# v1_5_Touch_USB.net
KiCad netlist of a schematic drawn in Altium Designer
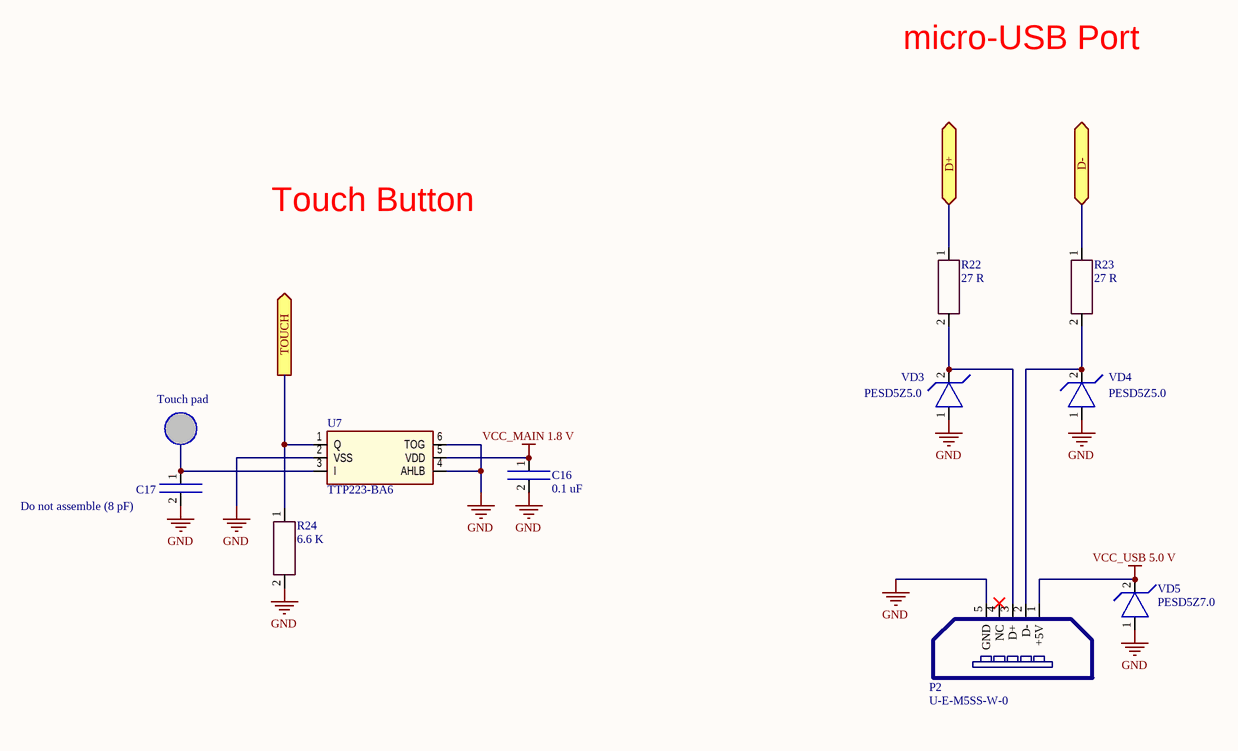
[diagram p0: v1.5 Touch & USB.SchDoc]

(export (version "E")
  (design (tool "Eeschema 10.0.6"))
  (components
    (comp (ref "C16")
      (value "0.1 uF")
      (footprint "Ungravity Library:0402")
      (libsource (lib "Ungravity Library") (part "Capasistor"))
    )
    (comp (ref "C17")
      (value "Do not assemble (8 pF)")
      (footprint "Ungravity Library:0402")
      (libsource (lib "Ungravity Library") (part "Capasistor"))
    )
    (comp (ref "P2")
      (value "U-E-M5SS-W-0")
      (footprint "Ungravity Library:U-E-M5SS-W-0")
      (libsource (lib "Ungravity Library") (part "micro-USB port"))
    )
    (comp (ref "R22")
      (value "27 R")
      (footprint "Ungravity Library:0402")
      (libsource (lib "Ungravity Library") (part "Resistor"))
    )
    (comp (ref "R23")
      (value "27 R")
      (footprint "Ungravity Library:0402")
      (libsource (lib "Ungravity Library") (part "Resistor"))
    )
    (comp (ref "R24")
      (value "6.6 K")
      (footprint "Ungravity Library:0402")
      (libsource (lib "Ungravity Library") (part "Resistor"))
    )
    (comp (ref "U7")
      (value "TTP223-BA6")
      (footprint "Ungravity Library:SOT23-6")
      (libsource (lib "Ungravity Library") (part "TTP223-BA6"))
    )
    (comp (ref "VD3")
      (value "PESD5Z5.0")
      (footprint "Ungravity Library:SOD-523")
      (libsource (lib "Ungravity Library") (part "Stabilitron"))
    )
    (comp (ref "VD4")
      (value "PESD5Z5.0")
      (footprint "Ungravity Library:SOD-523")
      (libsource (lib "Ungravity Library") (part "Stabilitron"))
    )
    (comp (ref "VD5")
      (value "PESD5Z7.0")
      (footprint "Ungravity Library:SOD-523")
      (libsource (lib "Ungravity Library") (part "Stabilitron"))
    )
  )
  (nets
    (net (code "1") (name "/D+") (class "Default")
      (node (ref "R22") (pin "1") (pinfunction "1_1") (pintype "passive"))
    )
    (net (code "2") (name "/D-") (class "Default")
      (node (ref "R23") (pin "1") (pinfunction "1_1") (pintype "passive"))
    )
    (net (code "3") (name "/TOUCH") (class "Default")
      (node (ref "R24") (pin "1") (pinfunction "1_1") (pintype "passive"))
      (node (ref "U7") (pin "1") (pinfunction "Q_1") (pintype "passive"))
    )
    (net (code "4") (name "GND") (class "Default")
      (node (ref "C16") (pin "2") (pinfunction "2_2") (pintype "passive"))
      (node (ref "C17") (pin "2") (pinfunction "2_2") (pintype "passive"))
      (node (ref "P2") (pin "5") (pinfunction "GND_5") (pintype "passive"))
      (node (ref "R24") (pin "2") (pinfunction "2_2") (pintype "passive"))
      (node (ref "U7") (pin "2") (pinfunction "VSS_2") (pintype "passive"))
      (node (ref "U7") (pin "4") (pinfunction "AHLB_4") (pintype "passive"))
      (node (ref "U7") (pin "6") (pinfunction "TOG_6") (pintype "passive"))
      (node (ref "VD3") (pin "1") (pinfunction "1_1") (pintype "passive"))
      (node (ref "VD4") (pin "1") (pinfunction "1_1") (pintype "passive"))
      (node (ref "VD5") (pin "1") (pinfunction "1_1") (pintype "passive"))
    )
    (net (code "5") (name "Net-(P2-D+)") (class "Default")
      (node (ref "P2") (pin "3") (pinfunction "D+_3") (pintype "passive"))
      (node (ref "R22") (pin "2") (pinfunction "2_2") (pintype "passive"))
      (node (ref "VD3") (pin "2") (pinfunction "2_2") (pintype "passive"))
    )
    (net (code "6") (name "Net-(P2-D-)") (class "Default")
      (node (ref "P2") (pin "2") (pinfunction "D-_2") (pintype "passive"))
      (node (ref "R23") (pin "2") (pinfunction "2_2") (pintype "passive"))
      (node (ref "VD4") (pin "2") (pinfunction "2_2") (pintype "passive"))
    )
    (net (code "7") (name "Net-(U7-I)") (class "Default")
      (node (ref "C17") (pin "1") (pinfunction "1_1") (pintype "passive"))
      (node (ref "U7") (pin "3") (pinfunction "I_3") (pintype "passive"))
    )
    (net (code "8") (name "VCC_MAIN 1.8 V") (class "Default")
      (node (ref "C16") (pin "1") (pinfunction "1_1") (pintype "passive"))
      (node (ref "U7") (pin "5") (pinfunction "VDD_5") (pintype "passive"))
    )
    (net (code "9") (name "VCC_USB 5.0 V") (class "Default")
      (node (ref "P2") (pin "1") (pinfunction "+5V_1") (pintype "passive"))
      (node (ref "VD5") (pin "2") (pinfunction "2_2") (pintype "passive"))
    )
    (net (code "10") (name "unconnected-(P2-NC-Pad4)") (class "Default")
      (node (ref "P2") (pin "4") (pinfunction "NC_4") (pintype "passive+no_connect"))
    )
  )
)
